# v12.net
KiCad netlist of a schematic drawn in EAGLE
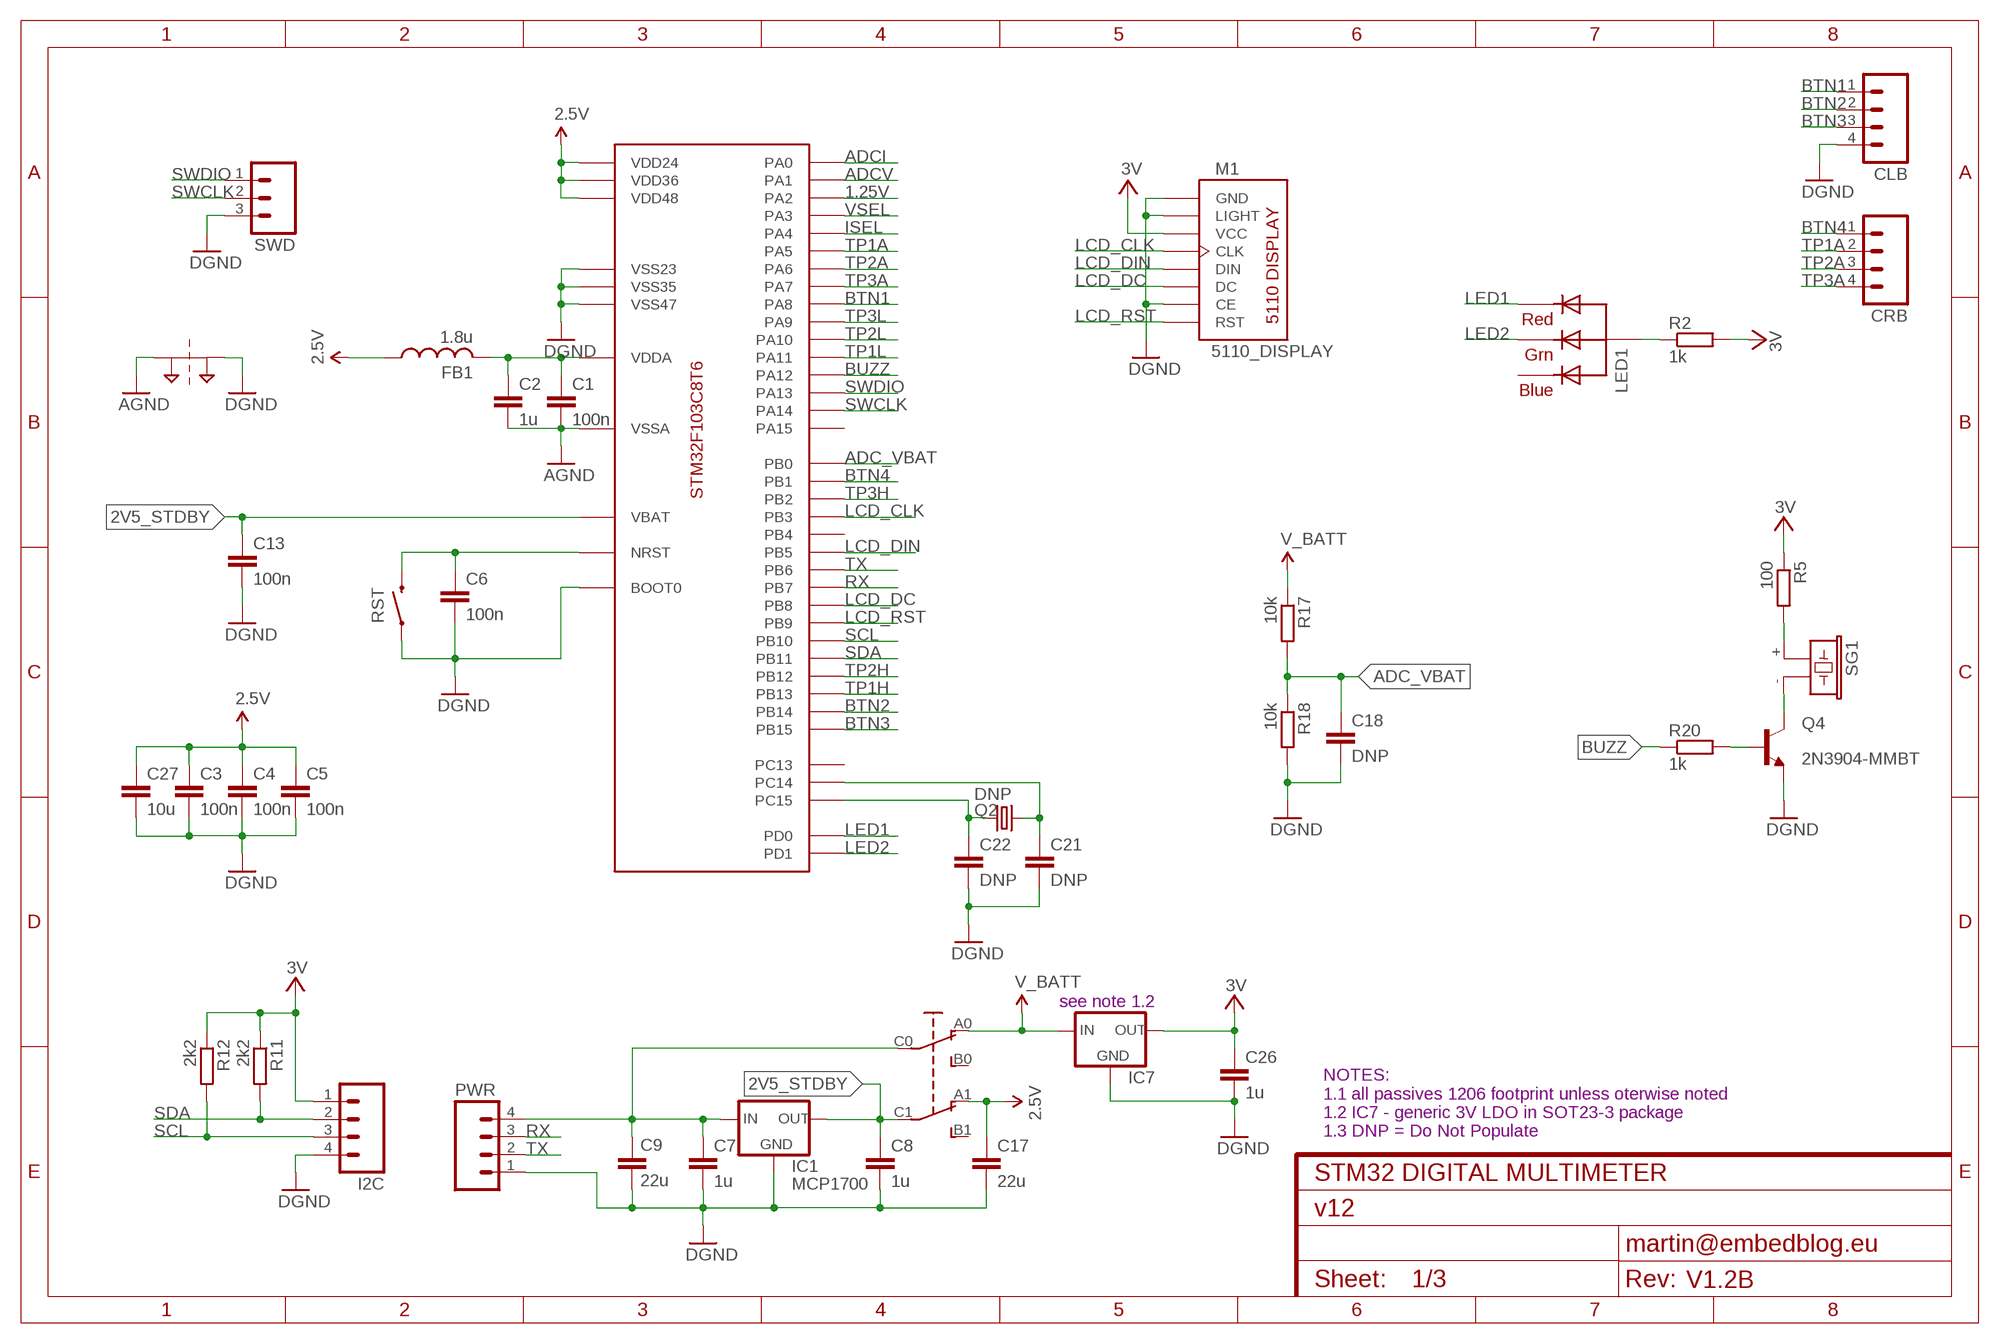
[diagram p0: schematic, sheet 1]
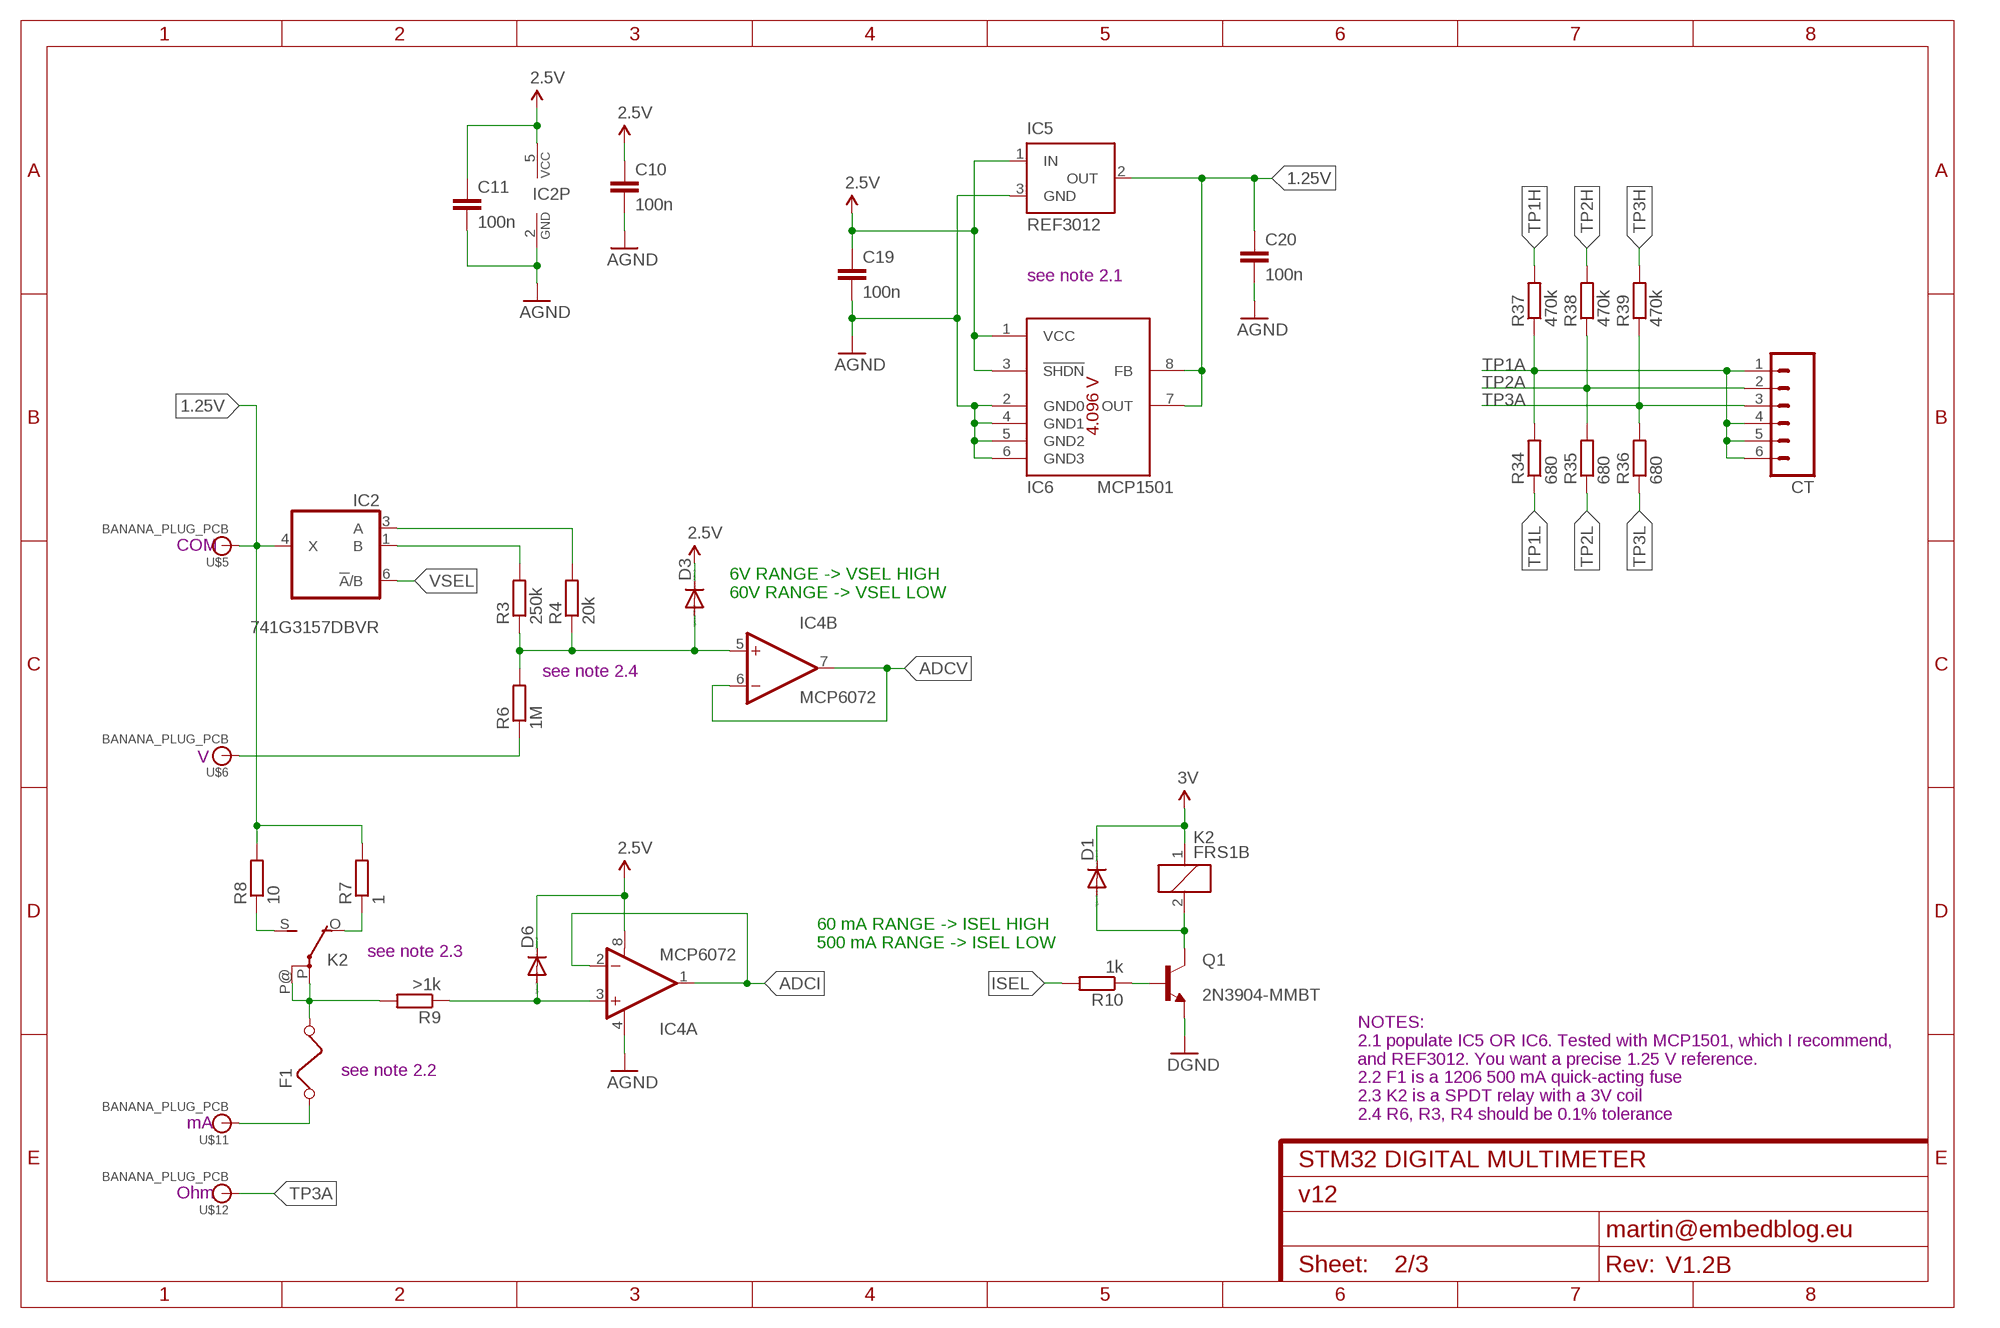
[diagram p1: schematic, sheet 2]
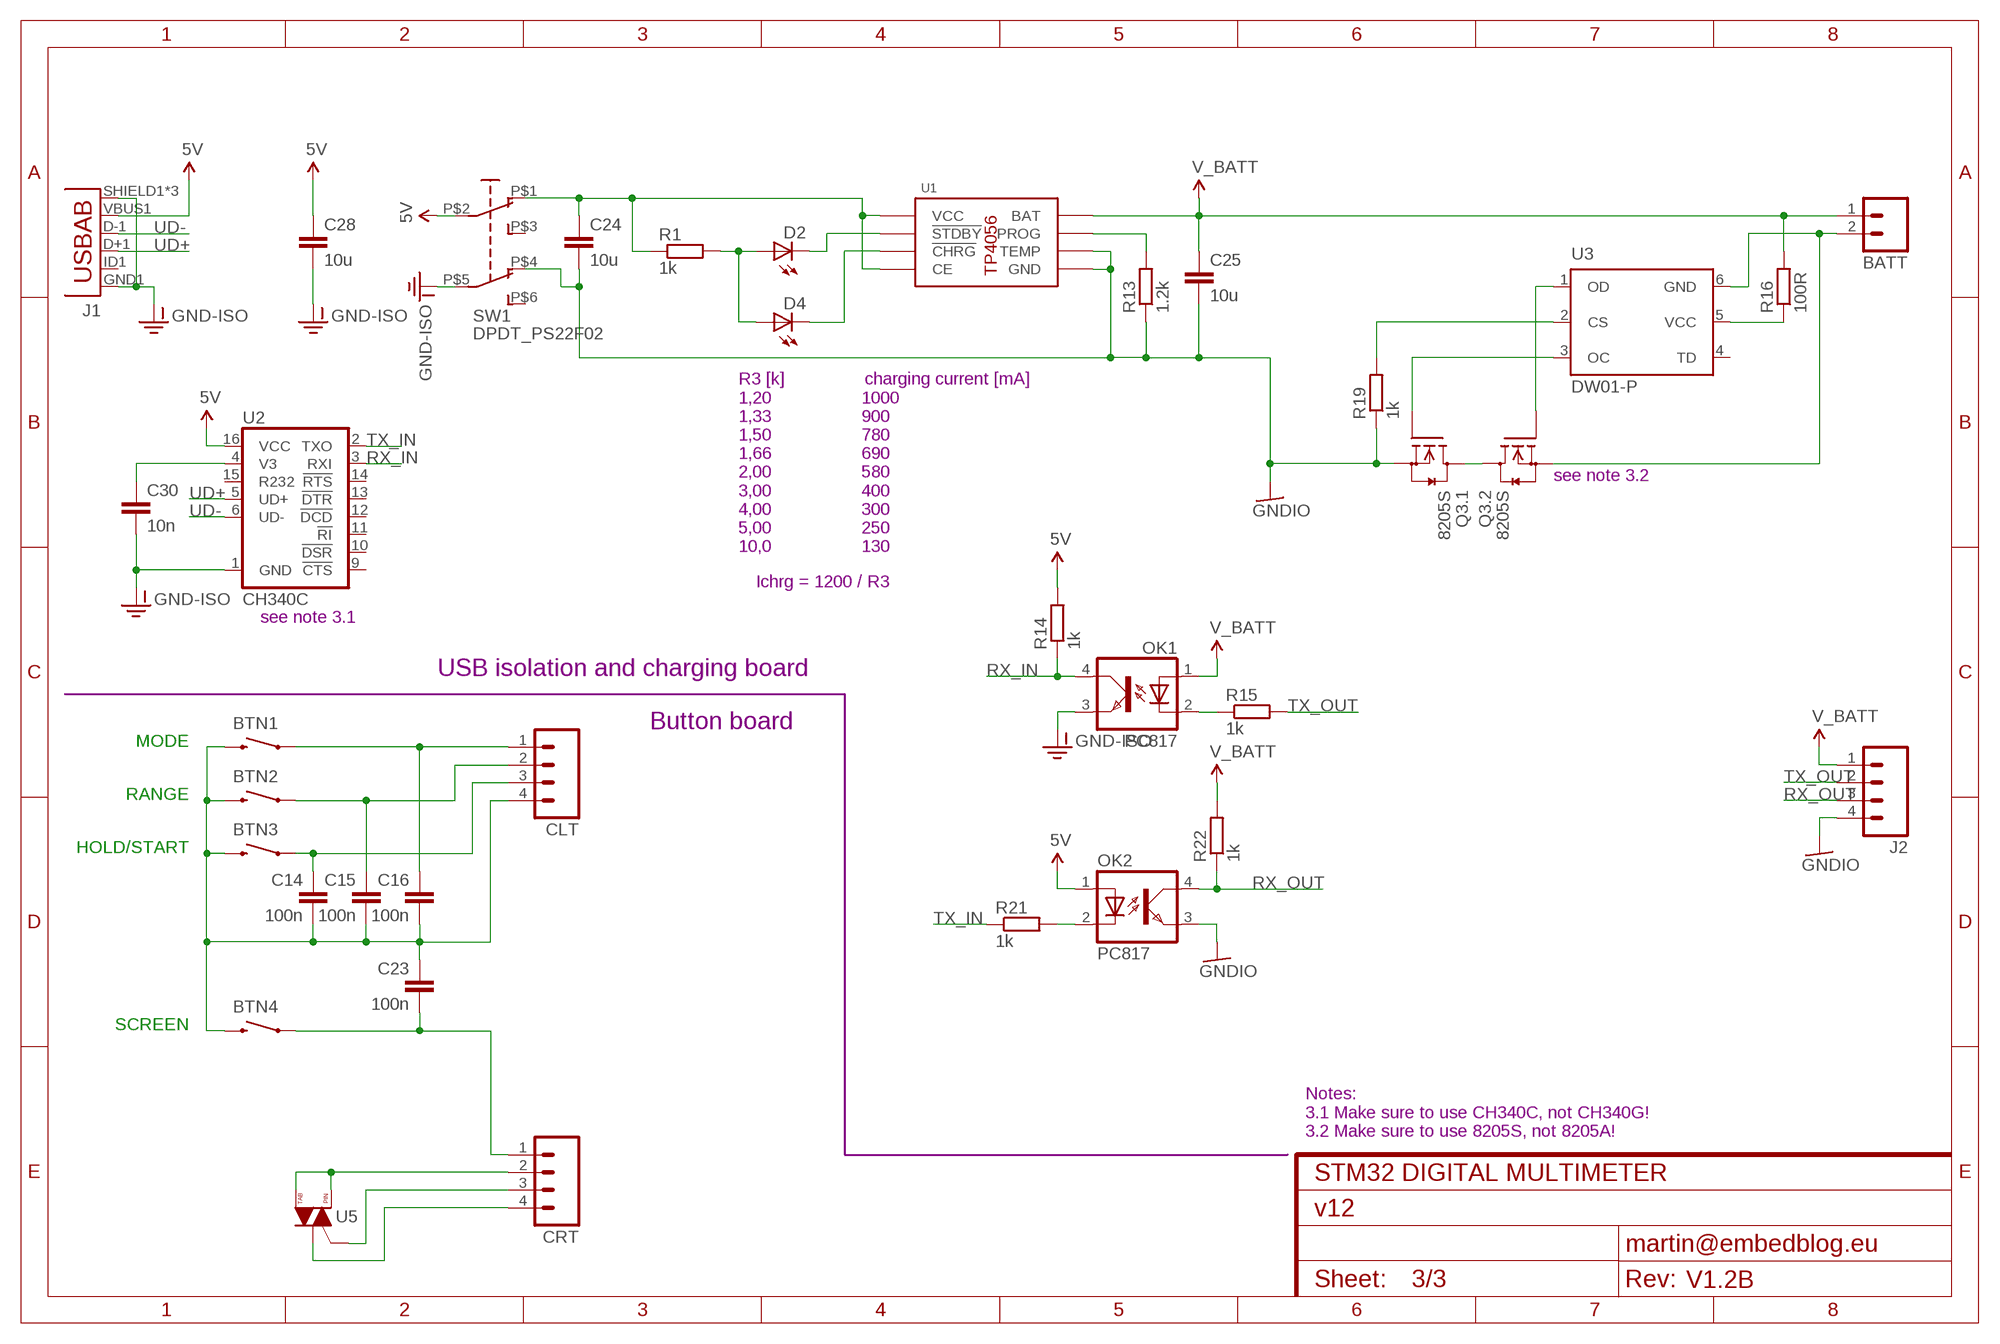
[diagram p2: schematic, sheet 3]

(export (version "E")
  (design (tool "Eeschema 10.0.6"))
  (components
    (comp (ref "C10")
      (value "100n")
      (footprint "eagle-import:1206")
      (libsource (lib "eagle-import") (part "CAP1206"))
    )
    (comp (ref "C11")
      (value "100n")
      (footprint "eagle-import:1206")
      (libsource (lib "eagle-import") (part "CAP1206"))
    )
    (comp (ref "C19")
      (value "100n")
      (footprint "eagle-import:C1206")
      (libsource (lib "eagle-import") (part "C-EUC1206"))
    )
    (comp (ref "C20")
      (value "100n")
      (footprint "eagle-import:C1206")
      (libsource (lib "eagle-import") (part "C-EUC1206"))
    )
    (comp (ref "CT")
      (value "M06SILK_FEMALE_PTH")
      (footprint "eagle-import:1X06")
      (libsource (lib "eagle-import") (part "M06SILK_FEMALE_PTH"))
    )
    (comp (ref "D1")
      (value "DIODE-MINIMELF")
      (footprint "eagle-import:MINIMELF")
      (libsource (lib "eagle-import") (part "DIODE-MINIMELF"))
    )
    (comp (ref "D3")
      (value "DIODE-MINIMELF")
      (footprint "eagle-import:MINIMELF")
      (libsource (lib "eagle-import") (part "DIODE-MINIMELF"))
    )
    (comp (ref "D6")
      (value "DIODE-MINIMELF")
      (footprint "eagle-import:MINIMELF")
      (libsource (lib "eagle-import") (part "DIODE-MINIMELF"))
    )
    (comp (ref "F1")
      (value "FUSEC")
      (footprint "eagle-import:1206")
      (libsource (lib "eagle-import") (part "FUSEC"))
    )
    (comp (ref "IC2")
      (value "741G3157DBVR")
      (footprint "eagle-import:DBV_R-PDSO-G6")
      (libsource (lib "eagle-import") (part "741G3157DBVR"))
    )
    (comp (ref "IC4")
      (value "MCP6072")
      (footprint "eagle-import:SO08")
      (libsource (lib "eagle-import") (part "OPAMP-DUALU"))
    )
    (comp (ref "IC5")
      (value "REF3012")
      (footprint "eagle-import:SOT23")
      (fields (field (name "MF") "MAXIM") (field (name "MPN") "MAX6520EUR-T"))
      (libsource (lib "eagle-import") (part "MAX6520"))
    )
    (comp (ref "IC6")
      (value "MCP1501")
      (footprint "eagle-import:SO08")
      (libsource (lib "eagle-import") (part "MCP1501"))
    )
    (comp (ref "K2")
      (value "FRS1B")
      (footprint "eagle-import:FRS1B")
      (libsource (lib "eagle-import") (part "FRS1B"))
    )
    (comp (ref "Q1")
      (value "2N3904-MMBT")
      (footprint "eagle-import:SOT23")
      (libsource (lib "eagle-import") (part "2N3904-MMBT"))
    )
    (comp (ref "R3")
      (value "250k")
      (footprint "eagle-import:R1206")
      (libsource (lib "eagle-import") (part "R-EU_R1206"))
    )
    (comp (ref "R4")
      (value "20k")
      (footprint "eagle-import:R1206")
      (libsource (lib "eagle-import") (part "R-EU_R1206"))
    )
    (comp (ref "R6")
      (value "1M")
      (footprint "eagle-import:R1206")
      (libsource (lib "eagle-import") (part "R-EU_R1206"))
    )
    (comp (ref "R7")
      (value "1")
      (footprint "eagle-import:R1206")
      (libsource (lib "eagle-import") (part "R-EU_R1206"))
    )
    (comp (ref "R8")
      (value "10")
      (footprint "eagle-import:R1206")
      (libsource (lib "eagle-import") (part "R-EU_R1206"))
    )
    (comp (ref "R9")
      (value ">1k")
      (footprint "eagle-import:R1206")
      (libsource (lib "eagle-import") (part "R-EU_R1206"))
    )
    (comp (ref "R10")
      (value "1k")
      (footprint "eagle-import:R1206")
      (libsource (lib "eagle-import") (part "R-EU_R1206"))
    )
    (comp (ref "R34")
      (value "680")
      (footprint "eagle-import:R1206")
      (libsource (lib "eagle-import") (part "R-EU_R1206"))
    )
    (comp (ref "R35")
      (value "680")
      (footprint "eagle-import:R1206")
      (libsource (lib "eagle-import") (part "R-EU_R1206"))
    )
    (comp (ref "R36")
      (value "680")
      (footprint "eagle-import:R1206")
      (libsource (lib "eagle-import") (part "R-EU_R1206"))
    )
    (comp (ref "R37")
      (value "470k")
      (footprint "eagle-import:R1206")
      (libsource (lib "eagle-import") (part "R-EU_R1206"))
    )
    (comp (ref "R38")
      (value "470k")
      (footprint "eagle-import:R1206")
      (libsource (lib "eagle-import") (part "R-EU_R1206"))
    )
    (comp (ref "R39")
      (value "470k")
      (footprint "eagle-import:R1206")
      (libsource (lib "eagle-import") (part "R-EU_R1206"))
    )
    (comp (ref "U$5")
      (value "BANANA_PLUG_PCB")
      (footprint "eagle-import:BANANA_6MMHOLE")
      (libsource (lib "eagle-import") (part "BANANA_PLUG_PCB"))
    )
    (comp (ref "U$6")
      (value "BANANA_PLUG_PCB")
      (footprint "eagle-import:BANANA_6MMHOLE")
      (libsource (lib "eagle-import") (part "BANANA_PLUG_PCB"))
    )
    (comp (ref "U$11")
      (value "BANANA_PLUG_PCB")
      (footprint "eagle-import:BANANA_6MMHOLE")
      (libsource (lib "eagle-import") (part "BANANA_PLUG_PCB"))
    )
    (comp (ref "U$12")
      (value "BANANA_PLUG_PCB")
      (footprint "eagle-import:BANANA_6MMHOLE")
      (libsource (lib "eagle-import") (part "BANANA_PLUG_PCB"))
    )
    (comp (ref "BATT")
      (value "M02PTH3")
      (footprint "eagle-import:1X02_LONGPADS")
      (libsource (lib "eagle-import") (part "M02PTH3"))
    )
    (comp (ref "BTN1")
      (value "SWITCH-MOMENTARY-2PTH")
      (footprint "eagle-import:TACTILE-PTH")
      (libsource (lib "eagle-import") (part "SWITCH-MOMENTARY-2PTH"))
    )
    (comp (ref "BTN2")
      (value "SWITCH-MOMENTARY-2PTH")
      (footprint "eagle-import:TACTILE-PTH")
      (libsource (lib "eagle-import") (part "SWITCH-MOMENTARY-2PTH"))
    )
    (comp (ref "BTN3")
      (value "SWITCH-MOMENTARY-2PTH")
      (footprint "eagle-import:TACTILE-PTH")
      (libsource (lib "eagle-import") (part "SWITCH-MOMENTARY-2PTH"))
    )
    (comp (ref "BTN4")
      (value "SWITCH-MOMENTARY-2PTH")
      (footprint "eagle-import:TACTILE-PTH")
      (libsource (lib "eagle-import") (part "SWITCH-MOMENTARY-2PTH"))
    )
    (comp (ref "C14")
      (value "100n")
      (footprint "eagle-import:C1206")
      (libsource (lib "eagle-import") (part "C-EUC1206"))
    )
    (comp (ref "C15")
      (value "100n")
      (footprint "eagle-import:C1206")
      (libsource (lib "eagle-import") (part "C-EUC1206"))
    )
    (comp (ref "C16")
      (value "100n")
      (footprint "eagle-import:C1206")
      (libsource (lib "eagle-import") (part "C-EUC1206"))
    )
    (comp (ref "C23")
      (value "100n")
      (footprint "eagle-import:C1206")
      (libsource (lib "eagle-import") (part "C-EUC1206"))
    )
    (comp (ref "C24")
      (value "10u")
      (footprint "eagle-import:C1206")
      (libsource (lib "eagle-import") (part "C-EUC1206"))
    )
    (comp (ref "C25")
      (value "10u")
      (footprint "eagle-import:C1206")
      (libsource (lib "eagle-import") (part "C-EUC1206"))
    )
    (comp (ref "C28")
      (value "10u")
      (footprint "eagle-import:C1206")
      (libsource (lib "eagle-import") (part "C-EUC1206"))
    )
    (comp (ref "C30")
      (value "10n")
      (footprint "eagle-import:C1206")
      (libsource (lib "eagle-import") (part "C-EUC1206"))
    )
    (comp (ref "CLT")
      (value "M04PTH")
      (footprint "eagle-import:1X04@1")
      (libsource (lib "eagle-import") (part "M04PTH"))
    )
    (comp (ref "CRT")
      (value "M04PTH")
      (footprint "eagle-import:1X04@1")
      (libsource (lib "eagle-import") (part "M04PTH"))
    )
    (comp (ref "D2")
      (value "LEDCHIPLED_1206")
      (footprint "eagle-import:CHIPLED_1206")
      (libsource (lib "eagle-import") (part "LEDCHIPLED_1206"))
    )
    (comp (ref "D4")
      (value "LEDCHIPLED_1206")
      (footprint "eagle-import:CHIPLED_1206")
      (libsource (lib "eagle-import") (part "LEDCHIPLED_1206"))
    )
    (comp (ref "J1")
      (value "USB-ABCONN-11794")
      (footprint "eagle-import:USB-AB-MICRO-SMD_V03")
      (libsource (lib "eagle-import") (part "USB-ABCONN-11794"))
    )
    (comp (ref "J2")
      (value "M04PTH")
      (footprint "eagle-import:1X04@1")
      (libsource (lib "eagle-import") (part "M04PTH"))
    )
    (comp (ref "OK1")
      (value "PC817")
      (footprint "eagle-import:DIL04")
      (fields (field (name "MPN") "PC817X4J000F"))
      (libsource (lib "eagle-import") (part "PC817"))
    )
    (comp (ref "OK2")
      (value "PC817")
      (footprint "eagle-import:DIL04")
      (fields (field (name "MPN") "PC817X4J000F"))
      (libsource (lib "eagle-import") (part "PC817"))
    )
    (comp (ref "Q3")
      (value "8205S")
      (footprint "eagle-import:SSOT-6")
      (libsource (lib "eagle-import") (part "FDC6305N"))
    )
    (comp (ref "R1")
      (value "1k")
      (footprint "eagle-import:R1206")
      (libsource (lib "eagle-import") (part "R-EU_R1206"))
    )
    (comp (ref "R13")
      (value "1.2k")
      (footprint "eagle-import:R1206")
      (libsource (lib "eagle-import") (part "R-EU_R1206"))
    )
    (comp (ref "R14")
      (value "1k")
      (footprint "eagle-import:R1206")
      (libsource (lib "eagle-import") (part "R-EU_R1206"))
    )
    (comp (ref "R15")
      (value "1k")
      (footprint "eagle-import:R1206")
      (libsource (lib "eagle-import") (part "R-EU_R1206"))
    )
    (comp (ref "R16")
      (value "100R")
      (footprint "eagle-import:R1206")
      (libsource (lib "eagle-import") (part "R-EU_R1206"))
    )
    (comp (ref "R19")
      (value "1k")
      (footprint "eagle-import:R1206")
      (libsource (lib "eagle-import") (part "R-EU_R1206"))
    )
    (comp (ref "R21")
      (value "1k")
      (footprint "eagle-import:R1206")
      (libsource (lib "eagle-import") (part "R-EU_R1206"))
    )
    (comp (ref "R22")
      (value "1k")
      (footprint "eagle-import:R1206")
      (libsource (lib "eagle-import") (part "R-EU_R1206"))
    )
    (comp (ref "SW1")
      (value "DPDT_PS22F02")
      (footprint "eagle-import:PS22_L02_DPDT_SW")
      (libsource (lib "eagle-import") (part "DPDT_PS22F02"))
    )
    (comp (ref "U1")
      (value "TP4056")
      (footprint "eagle-import:SOP8")
      (libsource (lib "eagle-import") (part "TP4056"))
    )
    (comp (ref "U2")
      (value "CH340C")
      (footprint "eagle-import:SO016")
      (libsource (lib "eagle-import") (part "CH340C"))
    )
    (comp (ref "U3")
      (value "DW01-P")
      (footprint "eagle-import:SOT23-6L")
      (libsource (lib "eagle-import") (part "DW01-P"))
    )
    (comp (ref "U5")
      (value "TRIAC-HPSMD")
      (footprint "eagle-import:SOT223")
      (libsource (lib "eagle-import") (part "TRIAC-HPSMD"))
    )
    (comp (ref "C1")
      (value "100n")
      (footprint "eagle-import:C1206")
      (libsource (lib "eagle-import") (part "C-EUC1206"))
    )
    (comp (ref "C2")
      (value "1u")
      (footprint "eagle-import:C1206")
      (libsource (lib "eagle-import") (part "C-EUC1206"))
    )
    (comp (ref "C3")
      (value "100n")
      (footprint "eagle-import:C1206")
      (libsource (lib "eagle-import") (part "C-EUC1206"))
    )
    (comp (ref "C4")
      (value "100n")
      (footprint "eagle-import:C1206")
      (libsource (lib "eagle-import") (part "C-EUC1206"))
    )
    (comp (ref "C5")
      (value "100n")
      (footprint "eagle-import:C1206")
      (libsource (lib "eagle-import") (part "C-EUC1206"))
    )
    (comp (ref "C6")
      (value "100n")
      (footprint "eagle-import:C1206")
      (libsource (lib "eagle-import") (part "C-EUC1206"))
    )
    (comp (ref "C7")
      (value "1u")
      (footprint "eagle-import:C1206")
      (libsource (lib "eagle-import") (part "C-EUC1206"))
    )
    (comp (ref "C8")
      (value "1u")
      (footprint "eagle-import:C1206")
      (libsource (lib "eagle-import") (part "C-EUC1206"))
    )
    (comp (ref "C9")
      (value "22u")
      (footprint "eagle-import:C1206")
      (libsource (lib "eagle-import") (part "C-EUC1206"))
    )
    (comp (ref "C13")
      (value "100n")
      (footprint "eagle-import:C1206")
      (libsource (lib "eagle-import") (part "C-EUC1206"))
    )
    (comp (ref "C17")
      (value "22u")
      (footprint "eagle-import:C1206")
      (libsource (lib "eagle-import") (part "C-EUC1206"))
    )
    (comp (ref "C18")
      (value "DNP")
      (footprint "eagle-import:C1206")
      (libsource (lib "eagle-import") (part "C-EUC1206"))
    )
    (comp (ref "C21")
      (value "DNP")
      (footprint "eagle-import:C1206")
      (libsource (lib "eagle-import") (part "C-EUC1206"))
    )
    (comp (ref "C22")
      (value "DNP")
      (footprint "eagle-import:C1206")
      (libsource (lib "eagle-import") (part "C-EUC1206"))
    )
    (comp (ref "C26")
      (value "1u")
      (footprint "eagle-import:C1206")
      (libsource (lib "eagle-import") (part "C-EUC1206"))
    )
    (comp (ref "C27")
      (value "10u")
      (footprint "eagle-import:C1206")
      (libsource (lib "eagle-import") (part "C-EUC1206"))
    )
    (comp (ref "CLB")
      (value "M04PTH")
      (footprint "eagle-import:1X04@1")
      (libsource (lib "eagle-import") (part "M04PTH"))
    )
    (comp (ref "CRB")
      (value "M04PTH")
      (footprint "eagle-import:1X04@1")
      (libsource (lib "eagle-import") (part "M04PTH"))
    )
    (comp (ref "FB1")
      (value "1.8u")
      (footprint "eagle-import:1206")
      (libsource (lib "eagle-import") (part "FERRITE-BEADC"))
    )
    (comp (ref "I2C")
      (value "M04PTH")
      (footprint "eagle-import:1X04@1")
      (libsource (lib "eagle-import") (part "M04PTH"))
    )
    (comp (ref "IC1")
      (value "MCP1700")
      (footprint "eagle-import:SOT23")
      (libsource (lib "eagle-import") (part "XC63FPM"))
    )
    (comp (ref "IC7")
      (value "XC63FPM")
      (footprint "eagle-import:SOT23")
      (libsource (lib "eagle-import") (part "XC63FPM"))
    )
    (comp (ref "LED1")
      (value "RGBLED_CA-5MM")
      (footprint "eagle-import:LED5MMRGB")
      (libsource (lib "eagle-import") (part "RGBLED_CA-5MM"))
    )
    (comp (ref "M1")
      (value "5110_DISPLAY")
      (footprint "eagle-import:5110_LAYOUT")
      (libsource (lib "eagle-import") (part "5110_DISPLAY"))
    )
    (comp (ref "PWR")
      (value "M04PTH")
      (footprint "eagle-import:1X04@1")
      (libsource (lib "eagle-import") (part "M04PTH"))
    )
    (comp (ref "Q2")
      (value "DNP")
      (footprint "eagle-import:TC26H")
      (libsource (lib "eagle-import") (part "CRYSTALTC26H"))
    )
    (comp (ref "Q4")
      (value "2N3904-MMBT")
      (footprint "eagle-import:SOT23")
      (libsource (lib "eagle-import") (part "2N3904-MMBT"))
    )
    (comp (ref "R2")
      (value "1k")
      (footprint "eagle-import:R1206")
      (libsource (lib "eagle-import") (part "R-EU_R1206"))
    )
    (comp (ref "R5")
      (value "100")
      (footprint "eagle-import:R1206")
      (libsource (lib "eagle-import") (part "R-EU_R1206"))
    )
    (comp (ref "R11")
      (value "2k2")
      (footprint "eagle-import:R1206")
      (libsource (lib "eagle-import") (part "R-EU_R1206"))
    )
    (comp (ref "R12")
      (value "2k2")
      (footprint "eagle-import:R1206")
      (libsource (lib "eagle-import") (part "R-EU_R1206"))
    )
    (comp (ref "R17")
      (value "10k")
      (footprint "eagle-import:R1206")
      (libsource (lib "eagle-import") (part "R-EU_R1206"))
    )
    (comp (ref "R18")
      (value "10k")
      (footprint "eagle-import:R1206")
      (libsource (lib "eagle-import") (part "R-EU_R1206"))
    )
    (comp (ref "R20")
      (value "1k")
      (footprint "eagle-import:R1206")
      (libsource (lib "eagle-import") (part "R-EU_R1206"))
    )
    (comp (ref "RST")
      (value "SWITCH-MOMENTARY-2SMD")
      (footprint "eagle-import:TACTILE-SWITCH-SMD")
      (libsource (lib "eagle-import") (part "SWITCH-MOMENTARY-2SMD"))
    )
    (comp (ref "SG1")
      (value "F/CM12P")
      (footprint "eagle-import:F_CM12P")
      (libsource (lib "eagle-import") (part "F/CM12P"))
    )
    (comp (ref "SJ1")
      (value "2PT_GND_TIE")
      (footprint "eagle-import:2PT_GND_TIE")
      (libsource (lib "eagle-import") (part "2PT_GND_TIE"))
    )
    (comp (ref "SWD")
      (value "M03PTH")
      (footprint "eagle-import:1X03")
      (libsource (lib "eagle-import") (part "M03PTH"))
    )
    (comp (ref "U$1")
      (value "STM32F103C8T6")
      (footprint "eagle-import:TQFP-48")
      (libsource (lib "eagle-import") (part "STM32F103C8T6"))
    )
    (comp (ref "U$16")
      (value "K3-2245_DPDT_SIDE_SWITCH")
      (footprint "eagle-import:K3-2245_DPDT_SWITCH")
      (libsource (lib "eagle-import") (part "K3-2245_DPDT_SIDE_SWITCH"))
    )
  )
  (nets
    (net (code "1") (name "1.25V") (class "Default")
      (node (ref "C20") (pin "1") (pinfunction "1_1") (pintype "passive"))
      (node (ref "IC2") (pin "4") (pinfunction "X_4") (pintype "bidirectional"))
      (node (ref "IC5") (pin "2") (pinfunction "OUT_2") (pintype "output"))
      (node (ref "IC6") (pin "7") (pinfunction "OUT_7") (pintype "bidirectional"))
      (node (ref "IC6") (pin "8") (pinfunction "FB_8") (pintype "bidirectional"))
      (node (ref "R7") (pin "2") (pinfunction "2_2") (pintype "passive"))
      (node (ref "R8") (pin "2") (pinfunction "2_2") (pintype "passive"))
      (node (ref "U$1") (pin "12") (pinfunction "PA2_12") (pintype "bidirectional"))
      (node (ref "U$5") (pin "P$1") (pinfunction "1_P$1") (pintype "passive"))
    )
    (net (code "2") (name "2.5V") (class "Default")
      (node (ref "C10") (pin "1") (pinfunction "1_1") (pintype "passive"))
      (node (ref "C11") (pin "1") (pinfunction "1_1") (pintype "passive"))
      (node (ref "C17") (pin "1") (pinfunction "1_1") (pintype "passive"))
      (node (ref "C19") (pin "1") (pinfunction "1_1") (pintype "passive"))
      (node (ref "C27") (pin "1") (pinfunction "1_1") (pintype "passive"))
      (node (ref "C3") (pin "1") (pinfunction "1_1") (pintype "passive"))
      (node (ref "C4") (pin "1") (pinfunction "1_1") (pintype "passive"))
      (node (ref "C5") (pin "1") (pinfunction "1_1") (pintype "passive"))
      (node (ref "D3") (pin "C") (pinfunction "C_C") (pintype "passive"))
      (node (ref "D6") (pin "C") (pinfunction "C_C") (pintype "passive"))
      (node (ref "FB1") (pin "1") (pinfunction "1_1") (pintype "passive"))
      (node (ref "IC2") (pin "5") (pinfunction "VCC_5") (pintype "power_in"))
      (node (ref "IC4") (pin "8") (pinfunction "V+_8") (pintype "power_in"))
      (node (ref "IC5") (pin "1") (pinfunction "IN_1") (pintype "input"))
      (node (ref "IC6") (pin "1") (pinfunction "VCC_1") (pintype "bidirectional"))
      (node (ref "IC6") (pin "3") (pinfunction "~{SHDN}_3") (pintype "bidirectional"))
      (node (ref "U$1") (pin "24") (pinfunction "VDD24_24") (pintype "input"))
      (node (ref "U$1") (pin "36") (pinfunction "VDD36_36") (pintype "input"))
      (node (ref "U$1") (pin "48") (pinfunction "VDD48_48") (pintype "input"))
      (node (ref "U$16") (pin "A1") (pinfunction "O1_A1") (pintype "passive"))
    )
    (net (code "3") (name "2V5_STDBY") (class "Default")
      (node (ref "C13") (pin "1") (pinfunction "1_1") (pintype "passive"))
      (node (ref "C8") (pin "1") (pinfunction "1_1") (pintype "passive"))
      (node (ref "IC1") (pin "2") (pinfunction "OUT_2") (pintype "passive"))
      (node (ref "U$1") (pin "1") (pinfunction "VBAT_1") (pintype "input"))
      (node (ref "U$16") (pin "C1") (pinfunction "P1_C1") (pintype "passive"))
    )
    (net (code "4") (name "3V") (class "Default")
      (node (ref "C26") (pin "1") (pinfunction "1_1") (pintype "passive"))
      (node (ref "D1") (pin "C") (pinfunction "C_C") (pintype "passive"))
      (node (ref "I2C") (pin "1") (pinfunction "1_1") (pintype "passive"))
      (node (ref "IC7") (pin "2") (pinfunction "OUT_2") (pintype "passive"))
      (node (ref "K2") (pin "1") (pinfunction "1_1") (pintype "passive"))
      (node (ref "M1") (pin "VCC") (pinfunction "VCC_VCC") (pintype "bidirectional"))
      (node (ref "R11") (pin "1") (pinfunction "1_1") (pintype "passive"))
      (node (ref "R12") (pin "1") (pinfunction "1_1") (pintype "passive"))
      (node (ref "R2") (pin "2") (pinfunction "2_2") (pintype "passive"))
      (node (ref "R5") (pin "1") (pinfunction "1_1") (pintype "passive"))
    )
    (net (code "5") (name "5V") (class "Default")
      (node (ref "C28") (pin "1") (pinfunction "1_1") (pintype "passive"))
      (node (ref "J1") (pin "VBUS1") (pinfunction "VBUS_VBUS1") (pintype "bidirectional"))
      (node (ref "OK2") (pin "1") (pinfunction "A_1") (pintype "passive"))
      (node (ref "R14") (pin "2") (pinfunction "2_2") (pintype "passive"))
      (node (ref "SW1") (pin "P$2") (pinfunction "P_P$2") (pintype "passive"))
      (node (ref "U2") (pin "16") (pinfunction "VCC_16") (pintype "bidirectional"))
    )
    (net (code "6") (name "ADCI") (class "Default")
      (node (ref "IC4") (pin "1") (pinfunction "OUT_1") (pintype "output"))
      (node (ref "IC4") (pin "2") (pinfunction "-IN_2") (pintype "input"))
      (node (ref "U$1") (pin "10") (pinfunction "PA0_10") (pintype "bidirectional"))
    )
    (net (code "7") (name "ADCV") (class "Default")
      (node (ref "IC4") (pin "6") (pinfunction "-IN_6") (pintype "input"))
      (node (ref "IC4") (pin "7") (pinfunction "OUT_7") (pintype "output"))
      (node (ref "U$1") (pin "11") (pinfunction "PA1_11") (pintype "bidirectional"))
    )
    (net (code "8") (name "ADC_VBAT") (class "Default")
      (node (ref "C18") (pin "1") (pinfunction "1_1") (pintype "passive"))
      (node (ref "R17") (pin "2") (pinfunction "2_2") (pintype "passive"))
      (node (ref "R18") (pin "1") (pinfunction "1_1") (pintype "passive"))
      (node (ref "U$1") (pin "18") (pinfunction "PB0_18") (pintype "bidirectional"))
    )
    (net (code "9") (name "AGND") (class "Default")
      (node (ref "C1") (pin "2") (pinfunction "2_2") (pintype "passive"))
      (node (ref "C10") (pin "2") (pinfunction "2_2") (pintype "passive"))
      (node (ref "C11") (pin "2") (pinfunction "2_2") (pintype "passive"))
      (node (ref "C19") (pin "2") (pinfunction "2_2") (pintype "passive"))
      (node (ref "C2") (pin "2") (pinfunction "2_2") (pintype "passive"))
      (node (ref "C20") (pin "2") (pinfunction "2_2") (pintype "passive"))
      (node (ref "IC2") (pin "2") (pinfunction "GND_2") (pintype "power_in"))
      (node (ref "IC4") (pin "4") (pinfunction "V-_4") (pintype "power_in"))
      (node (ref "IC5") (pin "3") (pinfunction "GND_3") (pintype "power_in"))
      (node (ref "IC6") (pin "2") (pinfunction "GND0_2") (pintype "bidirectional"))
      (node (ref "IC6") (pin "4") (pinfunction "GND1_4") (pintype "bidirectional"))
      (node (ref "IC6") (pin "5") (pinfunction "GND2_5") (pintype "bidirectional"))
      (node (ref "IC6") (pin "6") (pinfunction "GND3_6") (pintype "bidirectional"))
      (node (ref "SJ1") (pin "P$1") (pinfunction "P$1_P$1") (pintype "bidirectional"))
      (node (ref "U$1") (pin "8") (pinfunction "VSSA_8") (pintype "input"))
    )
    (net (code "10") (name "BTN1") (class "Default")
      (node (ref "CLB") (pin "1") (pinfunction "1_1") (pintype "passive"))
      (node (ref "U$1") (pin "29") (pinfunction "PA8_29") (pintype "bidirectional"))
    )
    (net (code "11") (name "BTN2") (class "Default")
      (node (ref "CLB") (pin "2") (pinfunction "2_2") (pintype "passive"))
      (node (ref "U$1") (pin "27") (pinfunction "PB14_27") (pintype "bidirectional"))
    )
    (net (code "12") (name "BTN3") (class "Default")
      (node (ref "CLB") (pin "3") (pinfunction "3_3") (pintype "passive"))
      (node (ref "U$1") (pin "28") (pinfunction "PB15_28") (pintype "bidirectional"))
    )
    (net (code "13") (name "BTN4") (class "Default")
      (node (ref "CRB") (pin "1") (pinfunction "1_1") (pintype "passive"))
      (node (ref "U$1") (pin "19") (pinfunction "PB1_19") (pintype "bidirectional"))
    )
    (net (code "14") (name "BUZZ") (class "Default")
      (node (ref "R20") (pin "1") (pinfunction "1_1") (pintype "passive"))
      (node (ref "U$1") (pin "33") (pinfunction "PA12_33") (pintype "bidirectional"))
    )
    (net (code "15") (name "GND") (class "Default")
      (node (ref "C13") (pin "2") (pinfunction "2_2") (pintype "passive"))
      (node (ref "C17") (pin "2") (pinfunction "2_2") (pintype "passive"))
      (node (ref "C18") (pin "2") (pinfunction "2_2") (pintype "passive"))
      (node (ref "C21") (pin "2") (pinfunction "2_2") (pintype "passive"))
      (node (ref "C22") (pin "2") (pinfunction "2_2") (pintype "passive"))
      (node (ref "C26") (pin "2") (pinfunction "2_2") (pintype "passive"))
      (node (ref "C27") (pin "2") (pinfunction "2_2") (pintype "passive"))
      (node (ref "C3") (pin "2") (pinfunction "2_2") (pintype "passive"))
      (node (ref "C4") (pin "2") (pinfunction "2_2") (pintype "passive"))
      (node (ref "C5") (pin "2") (pinfunction "2_2") (pintype "passive"))
      (node (ref "C6") (pin "2") (pinfunction "2_2") (pintype "passive"))
      (node (ref "C7") (pin "2") (pinfunction "2_2") (pintype "passive"))
      (node (ref "C8") (pin "2") (pinfunction "2_2") (pintype "passive"))
      (node (ref "C9") (pin "2") (pinfunction "2_2") (pintype "passive"))
      (node (ref "CLB") (pin "4") (pinfunction "4_4") (pintype "passive"))
      (node (ref "I2C") (pin "4") (pinfunction "4_4") (pintype "passive"))
      (node (ref "IC1") (pin "1") (pinfunction "GND_1") (pintype "input"))
      (node (ref "IC7") (pin "1") (pinfunction "GND_1") (pintype "input"))
      (node (ref "M1") (pin "CE") (pinfunction "CE_CE") (pintype "bidirectional"))
      (node (ref "M1") (pin "GND") (pinfunction "GND_GND") (pintype "bidirectional"))
      (node (ref "M1") (pin "LIGHT") (pinfunction "LIGHT_LIGHT") (pintype "bidirectional"))
      (node (ref "PWR") (pin "1") (pinfunction "1_1") (pintype "passive"))
      (node (ref "Q1") (pin "2") (pinfunction "E_2") (pintype "passive"))
      (node (ref "Q4") (pin "2") (pinfunction "E_2") (pintype "passive"))
      (node (ref "R18") (pin "2") (pinfunction "2_2") (pintype "passive"))
      (node (ref "RST") (pin "1") (pinfunction "1_1") (pintype "passive"))
      (node (ref "SJ1") (pin "P$2") (pinfunction "P$2_P$2") (pintype "bidirectional"))
      (node (ref "SWD") (pin "3") (pinfunction "3_3") (pintype "passive"))
      (node (ref "U$1") (pin "23") (pinfunction "VSS23_23") (pintype "input"))
      (node (ref "U$1") (pin "35") (pinfunction "VSS35_35") (pintype "input"))
      (node (ref "U$1") (pin "44") (pinfunction "BOOT0_44") (pintype "input"))
      (node (ref "U$1") (pin "47") (pinfunction "VSS47_47") (pintype "input"))
    )
    (net (code "16") (name "GND-ISO") (class "Default")
      (node (ref "C28") (pin "2") (pinfunction "2_2") (pintype "passive"))
      (node (ref "C30") (pin "2") (pinfunction "2_2") (pintype "passive"))
      (node (ref "J1") (pin "GND1") (pinfunction "GND_GND1") (pintype "bidirectional"))
      (node (ref "J1") (pin "SHIELD1") (pinfunction "SHIELD_SHIELD1") (pintype "bidirectional"))
      (node (ref "J1") (pin "SHIELD2") (pinfunction "SHIELD_SHIELD2") (pintype "bidirectional"))
      (node (ref "J1") (pin "SHIELD3") (pinfunction "SHIELD_SHIELD3") (pintype "bidirectional"))
      (node (ref "OK1") (pin "3") (pinfunction "EMIT_3") (pintype "passive"))
      (node (ref "SW1") (pin "P$5") (pinfunction "P1_P$5") (pintype "passive"))
      (node (ref "U2") (pin "1") (pinfunction "GND_1") (pintype "bidirectional"))
    )
    (net (code "17") (name "GNDIO") (class "Default")
      (node (ref "C24") (pin "2") (pinfunction "2_2") (pintype "passive"))
      (node (ref "C25") (pin "2") (pinfunction "2_2") (pintype "passive"))
      (node (ref "J2") (pin "4") (pinfunction "4_4") (pintype "passive"))
      (node (ref "OK2") (pin "3") (pinfunction "EMIT_3") (pintype "passive"))
      (node (ref "Q3") (pin "5") (pinfunction "S_5") (pintype "passive"))
      (node (ref "R13") (pin "1") (pinfunction "1_1") (pintype "passive"))
      (node (ref "R19") (pin "1") (pinfunction "1_1") (pintype "passive"))
      (node (ref "SW1") (pin "P$4") (pinfunction "O1_P$4") (pintype "passive"))
      (node (ref "U1") (pin "1") (pinfunction "TEMP_1") (pintype "bidirectional"))
      (node (ref "U1") (pin "3") (pinfunction "GND_3") (pintype "bidirectional"))
    )
    (net (code "18") (name "ISEL") (class "Default")
      (node (ref "R10") (pin "2") (pinfunction "2_2") (pintype "passive"))
      (node (ref "U$1") (pin "14") (pinfunction "PA4_14") (pintype "bidirectional"))
    )
    (net (code "19") (name "LCD_CLK") (class "Default")
      (node (ref "M1") (pin "CLK") (pinfunction "CLK_CLK") (pintype "bidirectional"))
      (node (ref "U$1") (pin "39") (pinfunction "PB3_39") (pintype "bidirectional"))
    )
    (net (code "20") (name "LCD_DC") (class "Default")
      (node (ref "M1") (pin "DC") (pinfunction "DC_DC") (pintype "bidirectional"))
      (node (ref "U$1") (pin "45") (pinfunction "PB8_45") (pintype "bidirectional"))
    )
    (net (code "21") (name "LCD_DIN") (class "Default")
      (node (ref "M1") (pin "DIN") (pinfunction "DIN_DIN") (pintype "bidirectional"))
      (node (ref "U$1") (pin "41") (pinfunction "PB5_41") (pintype "bidirectional"))
    )
    (net (code "22") (name "LCD_RST") (class "Default")
      (node (ref "M1") (pin "RST") (pinfunction "RST_RST") (pintype "bidirectional"))
      (node (ref "U$1") (pin "46") (pinfunction "PB9_46") (pintype "bidirectional"))
    )
    (net (code "23") (name "LED1") (class "Default")
      (node (ref "LED1") (pin "1") (pinfunction "RED_1") (pintype "bidirectional"))
      (node (ref "U$1") (pin "5") (pinfunction "PD0_5") (pintype "bidirectional"))
    )
    (net (code "24") (name "LED2") (class "Default")
      (node (ref "LED1") (pin "3") (pinfunction "GREEN_3") (pintype "bidirectional"))
      (node (ref "U$1") (pin "6") (pinfunction "PD1_6") (pintype "bidirectional"))
    )
    (net (code "25") (name "Net-(BTN1-2)") (class "Default")
      (node (ref "BTN1") (pin "3") (pinfunction "2_3") (pintype "passive"))
      (node (ref "BTN2") (pin "3") (pinfunction "2_3") (pintype "passive"))
      (node (ref "BTN3") (pin "3") (pinfunction "2_3") (pintype "passive"))
      (node (ref "BTN4") (pin "3") (pinfunction "2_3") (pintype "passive"))
      (node (ref "C14") (pin "2") (pinfunction "2_2") (pintype "passive"))
      (node (ref "C15") (pin "2") (pinfunction "2_2") (pintype "passive"))
      (node (ref "C16") (pin "2") (pinfunction "2_2") (pintype "passive"))
      (node (ref "C23") (pin "1") (pinfunction "1_1") (pintype "passive"))
      (node (ref "CLT") (pin "4") (pinfunction "4_4") (pintype "passive"))
    )
    (net (code "26") (name "Net-(BTN1-Pad1)") (class "Default")
      (node (ref "BTN1") (pin "1") (pinfunction "1_1") (pintype "passive"))
      (node (ref "C16") (pin "1") (pinfunction "1_1") (pintype "passive"))
      (node (ref "CLT") (pin "1") (pinfunction "1_1") (pintype "passive"))
    )
    (net (code "27") (name "Net-(BTN2-Pad1)") (class "Default")
      (node (ref "BTN2") (pin "1") (pinfunction "1_1") (pintype "passive"))
      (node (ref "C15") (pin "1") (pinfunction "1_1") (pintype "passive"))
      (node (ref "CLT") (pin "2") (pinfunction "2_2") (pintype "passive"))
    )
    (net (code "28") (name "Net-(BTN3-Pad1)") (class "Default")
      (node (ref "BTN3") (pin "1") (pinfunction "1_1") (pintype "passive"))
      (node (ref "C14") (pin "1") (pinfunction "1_1") (pintype "passive"))
      (node (ref "CLT") (pin "3") (pinfunction "3_3") (pintype "passive"))
    )
    (net (code "29") (name "Net-(BTN4-Pad1)") (class "Default")
      (node (ref "BTN4") (pin "1") (pinfunction "1_1") (pintype "passive"))
      (node (ref "C23") (pin "2") (pinfunction "2_2") (pintype "passive"))
      (node (ref "CRT") (pin "1") (pinfunction "1_1") (pintype "passive"))
    )
    (net (code "30") (name "Net-(CRT-Pad2)") (class "Default")
      (node (ref "CRT") (pin "2") (pinfunction "2_2") (pintype "passive"))
      (node (ref "U5") (pin "2") (pinfunction "T2_2") (pintype "passive"))
      (node (ref "U5") (pin "4") (pinfunction "T2_4") (pintype "passive"))
    )
    (net (code "31") (name "Net-(D2-PadA)") (class "Default")
      (node (ref "D2") (pin "A") (pinfunction "A_A") (pintype "passive"))
      (node (ref "D4") (pin "A") (pinfunction "A_A") (pintype "passive"))
      (node (ref "R1") (pin "2") (pinfunction "2_2") (pintype "passive"))
    )
    (net (code "32") (name "Net-(F1-Pad2)") (class "Default")
      (node (ref "F1") (pin "2") (pinfunction "2_2") (pintype "passive"))
      (node (ref "K2") (pin "P") (pinfunction "P_P") (pintype "passive"))
      (node (ref "K2") (pin "P@") (pinfunction "P_P@") (pintype "passive"))
      (node (ref "R9") (pin "2") (pinfunction "2_2") (pintype "passive"))
    )
    (net (code "33") (name "Net-(IC1-IN)") (class "Default")
      (node (ref "C7") (pin "1") (pinfunction "1_1") (pintype "passive"))
      (node (ref "C9") (pin "1") (pinfunction "1_1") (pintype "passive"))
      (node (ref "IC1") (pin "3") (pinfunction "IN_3") (pintype "input"))
      (node (ref "PWR") (pin "4") (pinfunction "4_4") (pintype "passive"))
      (node (ref "U$16") (pin "C0") (pinfunction "P_C0") (pintype "passive"))
    )
    (net (code "34") (name "Net-(IC2A-A)") (class "Default")
      (node (ref "IC2") (pin "3") (pinfunction "A_3") (pintype "bidirectional"))
      (node (ref "R4") (pin "2") (pinfunction "2_2") (pintype "passive"))
    )
    (net (code "35") (name "Net-(IC2A-B)") (class "Default")
      (node (ref "IC2") (pin "1") (pinfunction "B_1") (pintype "bidirectional"))
      (node (ref "R3") (pin "2") (pinfunction "2_2") (pintype "passive"))
    )
    (net (code "36") (name "Net-(IC4A-+IN)") (class "Default")
      (node (ref "D6") (pin "A") (pinfunction "A_A") (pintype "passive"))
      (node (ref "IC4") (pin "3") (pinfunction "+IN_3") (pintype "input"))
      (node (ref "R9") (pin "1") (pinfunction "1_1") (pintype "passive"))
    )
    (net (code "37") (name "Net-(IC4B-+IN)") (class "Default")
      (node (ref "D3") (pin "A") (pinfunction "A_A") (pintype "passive"))
      (node (ref "IC4") (pin "5") (pinfunction "+IN_5") (pintype "input"))
      (node (ref "R3") (pin "1") (pinfunction "1_1") (pintype "passive"))
      (node (ref "R4") (pin "1") (pinfunction "1_1") (pintype "passive"))
      (node (ref "R6") (pin "2") (pinfunction "2_2") (pintype "passive"))
    )
    (net (code "38") (name "Net-(K2-PadO)") (class "Default")
      (node (ref "K2") (pin "O") (pinfunction "O_O") (pintype "passive"))
      (node (ref "R7") (pin "1") (pinfunction "1_1") (pintype "passive"))
    )
    (net (code "39") (name "Net-(K2-PadS)") (class "Default")
      (node (ref "K2") (pin "S") (pinfunction "S_S") (pintype "passive"))
      (node (ref "R8") (pin "1") (pinfunction "1_1") (pintype "passive"))
    )
    (net (code "40") (name "Net-(LED1-VCC)") (class "Default")
      (node (ref "LED1") (pin "2") (pinfunction "VCC_2") (pintype "bidirectional"))
      (node (ref "R2") (pin "1") (pinfunction "1_1") (pintype "passive"))
    )
    (net (code "41") (name "Net-(OK1-C)") (class "Default")
      (node (ref "OK1") (pin "2") (pinfunction "C_2") (pintype "passive"))
      (node (ref "R15") (pin "1") (pinfunction "1_1") (pintype "passive"))
    )
    (net (code "42") (name "Net-(OK2-C)") (class "Default")
      (node (ref "OK2") (pin "2") (pinfunction "C_2") (pintype "passive"))
      (node (ref "R21") (pin "2") (pinfunction "2_2") (pintype "passive"))
    )
    (net (code "43") (name "Net-(Q1-B)") (class "Default")
      (node (ref "Q1") (pin "1") (pinfunction "B_1") (pintype "passive"))
      (node (ref "R10") (pin "1") (pinfunction "1_1") (pintype "passive"))
    )
    (net (code "44") (name "Net-(Q1-C)") (class "Default")
      (node (ref "D1") (pin "A") (pinfunction "A_A") (pintype "passive"))
      (node (ref "K2") (pin "2") (pinfunction "2_2") (pintype "passive"))
      (node (ref "Q1") (pin "3") (pinfunction "C_3") (pintype "passive"))
    )
    (net (code "45") (name "Net-(Q3A-D)") (class "Default")
      (node (ref "Q3") (pin "4") (pinfunction "D_4") (pintype "passive"))
      (node (ref "Q3") (pin "6") (pinfunction "D_6") (pintype "passive"))
    )
    (net (code "46") (name "Net-(Q3A-G)") (class "Default")
      (node (ref "Q3") (pin "1") (pinfunction "G_1") (pintype "passive"))
      (node (ref "U3") (pin "3") (pinfunction "OC_3") (pintype "power_in"))
    )
    (net (code "47") (name "Net-(Q3B-G)") (class "Default")
      (node (ref "Q3") (pin "3") (pinfunction "G_3") (pintype "passive"))
      (node (ref "U3") (pin "1") (pinfunction "OD_1") (pintype "power_in"))
    )
    (net (code "48") (name "Net-(Q3B-S)") (class "Default")
      (node (ref "BATT") (pin "2") (pinfunction "2_2") (pintype "passive"))
      (node (ref "Q3") (pin "2") (pinfunction "S_2") (pintype "passive"))
      (node (ref "U3") (pin "6") (pinfunction "GND_6") (pintype "output"))
    )
    (net (code "49") (name "Net-(Q4-B)") (class "Default")
      (node (ref "Q4") (pin "1") (pinfunction "B_1") (pintype "passive"))
      (node (ref "R20") (pin "2") (pinfunction "2_2") (pintype "passive"))
    )
    (net (code "50") (name "Net-(Q4-C)") (class "Default")
      (node (ref "Q4") (pin "3") (pinfunction "C_3") (pintype "passive"))
      (node (ref "SG1") (pin "-") (pinfunction "2_-") (pintype "passive"))
    )
    (net (code "51") (name "Net-(RST-2)") (class "Default")
      (node (ref "C6") (pin "1") (pinfunction "1_1") (pintype "passive"))
      (node (ref "RST") (pin "3") (pinfunction "2_3") (pintype "passive"))
      (node (ref "U$1") (pin "7") (pinfunction "NRST_7") (pintype "input"))
    )
    (net (code "52") (name "Net-(SG1-1)") (class "Default")
      (node (ref "R5") (pin "2") (pinfunction "2_2") (pintype "passive"))
      (node (ref "SG1") (pin "+") (pinfunction "1_+") (pintype "passive"))
    )
    (net (code "53") (name "Net-(SW1-O)") (class "Default")
      (node (ref "C24") (pin "1") (pinfunction "1_1") (pintype "passive"))
      (node (ref "R1") (pin "1") (pinfunction "1_1") (pintype "passive"))
      (node (ref "SW1") (pin "P$1") (pinfunction "O_P$1") (pintype "passive"))
      (node (ref "U1") (pin "4") (pinfunction "VCC_4") (pintype "bidirectional"))
      (node (ref "U1") (pin "8") (pinfunction "CE_8") (pintype "bidirectional"))
    )
    (net (code "54") (name "Net-(U$1-PC14)") (class "Default")
      (node (ref "C21") (pin "1") (pinfunction "1_1") (pintype "passive"))
      (node (ref "Q2") (pin "2") (pinfunction "2_2") (pintype "passive"))
      (node (ref "U$1") (pin "3") (pinfunction "PC14_3") (pintype "bidirectional"))
    )
    (net (code "55") (name "Net-(U$1-PC15)") (class "Default")
      (node (ref "C22") (pin "1") (pinfunction "1_1") (pintype "passive"))
      (node (ref "Q2") (pin "1") (pinfunction "1_1") (pintype "passive"))
      (node (ref "U$1") (pin "4") (pinfunction "PC15_4") (pintype "bidirectional"))
    )
    (net (code "56") (name "Net-(U$1-VDDA)") (class "Default")
      (node (ref "C1") (pin "1") (pinfunction "1_1") (pintype "passive"))
      (node (ref "C2") (pin "1") (pinfunction "1_1") (pintype "passive"))
      (node (ref "FB1") (pin "2") (pinfunction "2_2") (pintype "passive"))
      (node (ref "U$1") (pin "9") (pinfunction "VDDA_9") (pintype "input"))
    )
    (net (code "57") (name "Net-(U$6-1)") (class "Default")
      (node (ref "R6") (pin "1") (pinfunction "1_1") (pintype "passive"))
      (node (ref "U$6") (pin "P$1") (pinfunction "1_P$1") (pintype "passive"))
    )
    (net (code "58") (name "Net-(U$11-1)") (class "Default")
      (node (ref "F1") (pin "1") (pinfunction "1_1") (pintype "passive"))
      (node (ref "U$11") (pin "P$1") (pinfunction "1_P$1") (pintype "passive"))
    )
    (net (code "59") (name "Net-(U1-PROG)") (class "Default")
      (node (ref "R13") (pin "2") (pinfunction "2_2") (pintype "passive"))
      (node (ref "U1") (pin "2") (pinfunction "PROG_2") (pintype "bidirectional"))
    )
    (net (code "60") (name "Net-(U1-~{CHRG})") (class "Default")
      (node (ref "D4") (pin "C") (pinfunction "C_C") (pintype "passive"))
      (node (ref "U1") (pin "7") (pinfunction "~{CHRG}_7") (pintype "bidirectional"))
    )
    (net (code "61") (name "Net-(U1-~{STDBY})") (class "Default")
      (node (ref "D2") (pin "C") (pinfunction "C_C") (pintype "passive"))
      (node (ref "U1") (pin "6") (pinfunction "~{STDBY}_6") (pintype "bidirectional"))
    )
    (net (code "62") (name "Net-(U2-V3)") (class "Default")
      (node (ref "C30") (pin "1") (pinfunction "1_1") (pintype "passive"))
      (node (ref "U2") (pin "4") (pinfunction "V3_4") (pintype "bidirectional"))
    )
    (net (code "63") (name "Net-(U3-CS)") (class "Default")
      (node (ref "R19") (pin "2") (pinfunction "2_2") (pintype "passive"))
      (node (ref "U3") (pin "2") (pinfunction "CS_2") (pintype "input"))
    )
    (net (code "64") (name "Net-(U3-VCC)") (class "Default")
      (node (ref "R16") (pin "1") (pinfunction "1_1") (pintype "passive"))
      (node (ref "U3") (pin "5") (pinfunction "VCC_5") (pintype "input"))
    )
    (net (code "65") (name "Net-(U5-G)") (class "Default")
      (node (ref "CRT") (pin "3") (pinfunction "3_3") (pintype "passive"))
      (node (ref "U5") (pin "3") (pinfunction "G_3") (pintype "bidirectional"))
    )
    (net (code "66") (name "Net-(U5-T1)") (class "Default")
      (node (ref "CRT") (pin "4") (pinfunction "4_4") (pintype "passive"))
      (node (ref "U5") (pin "1") (pinfunction "T1_1") (pintype "bidirectional"))
    )
    (net (code "67") (name "RX") (class "Default")
      (node (ref "PWR") (pin "3") (pinfunction "3_3") (pintype "passive"))
      (node (ref "U$1") (pin "43") (pinfunction "PB7_43") (pintype "bidirectional"))
    )
    (net (code "68") (name "RX_IN") (class "Default")
      (node (ref "OK1") (pin "4") (pinfunction "COL_4") (pintype "passive"))
      (node (ref "R14") (pin "1") (pinfunction "1_1") (pintype "passive"))
      (node (ref "U2") (pin "3") (pinfunction "RXI_3") (pintype "bidirectional"))
    )
    (net (code "69") (name "RX_OUT") (class "Default")
      (node (ref "J2") (pin "3") (pinfunction "3_3") (pintype "passive"))
      (node (ref "OK2") (pin "4") (pinfunction "COL_4") (pintype "passive"))
      (node (ref "R22") (pin "1") (pinfunction "1_1") (pintype "passive"))
    )
    (net (code "70") (name "SCL") (class "Default")
      (node (ref "I2C") (pin "3") (pinfunction "3_3") (pintype "passive"))
      (node (ref "R12") (pin "2") (pinfunction "2_2") (pintype "passive"))
      (node (ref "U$1") (pin "21") (pinfunction "PB10_21") (pintype "bidirectional"))
    )
    (net (code "71") (name "SDA") (class "Default")
      (node (ref "I2C") (pin "2") (pinfunction "2_2") (pintype "passive"))
      (node (ref "R11") (pin "2") (pinfunction "2_2") (pintype "passive"))
      (node (ref "U$1") (pin "22") (pinfunction "PB11_22") (pintype "bidirectional"))
    )
    (net (code "72") (name "SWCLK") (class "Default")
      (node (ref "SWD") (pin "2") (pinfunction "2_2") (pintype "passive"))
      (node (ref "U$1") (pin "37") (pinfunction "PA14_37") (pintype "bidirectional"))
    )
    (net (code "73") (name "SWDIO") (class "Default")
      (node (ref "SWD") (pin "1") (pinfunction "1_1") (pintype "passive"))
      (node (ref "U$1") (pin "34") (pinfunction "PA13_34") (pintype "bidirectional"))
    )
    (net (code "74") (name "TP1A") (class "Default")
      (node (ref "CRB") (pin "2") (pinfunction "2_2") (pintype "passive"))
      (node (ref "CT") (pin "1") (pinfunction "1_1") (pintype "passive"))
      (node (ref "CT") (pin "4") (pinfunction "4_4") (pintype "passive"))
      (node (ref "CT") (pin "5") (pinfunction "5_5") (pintype "passive"))
      (node (ref "CT") (pin "6") (pinfunction "6_6") (pintype "passive"))
      (node (ref "R34") (pin "2") (pinfunction "2_2") (pintype "passive"))
      (node (ref "R37") (pin "1") (pinfunction "1_1") (pintype "passive"))
      (node (ref "U$1") (pin "15") (pinfunction "PA5_15") (pintype "bidirectional"))
    )
    (net (code "75") (name "TP1H") (class "Default")
      (node (ref "R37") (pin "2") (pinfunction "2_2") (pintype "passive"))
      (node (ref "U$1") (pin "26") (pinfunction "PB13_26") (pintype "bidirectional"))
    )
    (net (code "76") (name "TP1L") (class "Default")
      (node (ref "R34") (pin "1") (pinfunction "1_1") (pintype "passive"))
      (node (ref "U$1") (pin "32") (pinfunction "PA11_32") (pintype "bidirectional"))
    )
    (net (code "77") (name "TP2A") (class "Default")
      (node (ref "CRB") (pin "3") (pinfunction "3_3") (pintype "passive"))
      (node (ref "CT") (pin "2") (pinfunction "2_2") (pintype "passive"))
      (node (ref "R35") (pin "2") (pinfunction "2_2") (pintype "passive"))
      (node (ref "R38") (pin "1") (pinfunction "1_1") (pintype "passive"))
      (node (ref "U$1") (pin "16") (pinfunction "PA6_16") (pintype "bidirectional"))
    )
    (net (code "78") (name "TP2H") (class "Default")
      (node (ref "R38") (pin "2") (pinfunction "2_2") (pintype "passive"))
      (node (ref "U$1") (pin "25") (pinfunction "PB12_25") (pintype "bidirectional"))
    )
    (net (code "79") (name "TP2L") (class "Default")
      (node (ref "R35") (pin "1") (pinfunction "1_1") (pintype "passive"))
      (node (ref "U$1") (pin "31") (pinfunction "PA10_31") (pintype "bidirectional"))
    )
    (net (code "80") (name "TP3A") (class "Default")
      (node (ref "CRB") (pin "4") (pinfunction "4_4") (pintype "passive"))
      (node (ref "CT") (pin "3") (pinfunction "3_3") (pintype "passive"))
      (node (ref "R36") (pin "2") (pinfunction "2_2") (pintype "passive"))
      (node (ref "R39") (pin "1") (pinfunction "1_1") (pintype "passive"))
      (node (ref "U$1") (pin "17") (pinfunction "PA7_17") (pintype "bidirectional"))
      (node (ref "U$12") (pin "P$1") (pinfunction "1_P$1") (pintype "passive"))
    )
    (net (code "81") (name "TP3H") (class "Default")
      (node (ref "R39") (pin "2") (pinfunction "2_2") (pintype "passive"))
      (node (ref "U$1") (pin "20") (pinfunction "PB2_20") (pintype "bidirectional"))
    )
    (net (code "82") (name "TP3L") (class "Default")
      (node (ref "R36") (pin "1") (pinfunction "1_1") (pintype "passive"))
      (node (ref "U$1") (pin "30") (pinfunction "PA9_30") (pintype "bidirectional"))
    )
    (net (code "83") (name "TX") (class "Default")
      (node (ref "PWR") (pin "2") (pinfunction "2_2") (pintype "passive"))
      (node (ref "U$1") (pin "42") (pinfunction "PB6_42") (pintype "bidirectional"))
    )
    (net (code "84") (name "TX_IN") (class "Default")
      (node (ref "R21") (pin "1") (pinfunction "1_1") (pintype "passive"))
      (node (ref "U2") (pin "2") (pinfunction "TXO_2") (pintype "bidirectional"))
    )
    (net (code "85") (name "TX_OUT") (class "Default")
      (node (ref "J2") (pin "2") (pinfunction "2_2") (pintype "passive"))
      (node (ref "R15") (pin "2") (pinfunction "2_2") (pintype "passive"))
    )
    (net (code "86") (name "UD+") (class "Default")
      (node (ref "J1") (pin "D+1") (pinfunction "D+_D+1") (pintype "bidirectional"))
      (node (ref "U2") (pin "5") (pinfunction "UD+_5") (pintype "bidirectional"))
    )
    (net (code "87") (name "UD-") (class "Default")
      (node (ref "J1") (pin "D-1") (pinfunction "D-_D-1") (pintype "bidirectional"))
      (node (ref "U2") (pin "6") (pinfunction "UD-_6") (pintype "bidirectional"))
    )
    (net (code "88") (name "VSEL") (class "Default")
      (node (ref "IC2") (pin "6") (pinfunction "~{A}/B_6") (pintype "input"))
      (node (ref "U$1") (pin "13") (pinfunction "PA3_13") (pintype "bidirectional"))
    )
    (net (code "89") (name "V_BATT") (class "Default")
      (node (ref "BATT") (pin "1") (pinfunction "1_1") (pintype "passive"))
      (node (ref "C25") (pin "1") (pinfunction "1_1") (pintype "passive"))
      (node (ref "IC7") (pin "3") (pinfunction "IN_3") (pintype "input"))
      (node (ref "J2") (pin "1") (pinfunction "1_1") (pintype "passive"))
      (node (ref "OK1") (pin "1") (pinfunction "A_1") (pintype "passive"))
      (node (ref "R16") (pin "2") (pinfunction "2_2") (pintype "passive"))
      (node (ref "R17") (pin "1") (pinfunction "1_1") (pintype "passive"))
      (node (ref "R22") (pin "2") (pinfunction "2_2") (pintype "passive"))
      (node (ref "U$16") (pin "A0") (pinfunction "O_A0") (pintype "passive"))
      (node (ref "U1") (pin "5") (pinfunction "BAT_5") (pintype "bidirectional"))
    )
    (net (code "90") (name "unconnected-(J1-USBID-PadID1)") (class "Default")
      (node (ref "J1") (pin "ID1") (pinfunction "USBID_ID1") (pintype "bidirectional"))
    )
    (net (code "91") (name "unconnected-(LED1-BLUE-Pad4)") (class "Default")
      (node (ref "LED1") (pin "4") (pinfunction "BLUE_4") (pintype "bidirectional"))
    )
    (net (code "92") (name "unconnected-(SW1-S-PadP$3)") (class "Default")
      (node (ref "SW1") (pin "P$3") (pinfunction "S_P$3") (pintype "passive"))
    )
    (net (code "93") (name "unconnected-(SW1-S1-PadP$6)") (class "Default")
      (node (ref "SW1") (pin "P$6") (pinfunction "S1_P$6") (pintype "passive"))
    )
    (net (code "94") (name "unconnected-(U$1-PA15-Pad38)") (class "Default")
      (node (ref "U$1") (pin "38") (pinfunction "PA15_38") (pintype "bidirectional"))
    )
    (net (code "95") (name "unconnected-(U$1-PB4-Pad40)") (class "Default")
      (node (ref "U$1") (pin "40") (pinfunction "PB4_40") (pintype "bidirectional"))
    )
    (net (code "96") (name "unconnected-(U$1-PC13-Pad2)") (class "Default")
      (node (ref "U$1") (pin "2") (pinfunction "PC13_2") (pintype "bidirectional"))
    )
    (net (code "97") (name "unconnected-(U$16-S-PadB0)") (class "Default")
      (node (ref "U$16") (pin "B0") (pinfunction "S_B0") (pintype "passive"))
    )
    (net (code "98") (name "unconnected-(U$16-S1-PadB1)") (class "Default")
      (node (ref "U$16") (pin "B1") (pinfunction "S1_B1") (pintype "passive"))
    )
    (net (code "99") (name "unconnected-(U2-R232-Pad15)") (class "Default")
      (node (ref "U2") (pin "15") (pinfunction "R232_15") (pintype "bidirectional"))
    )
    (net (code "100") (name "unconnected-(U2-~{CTS}-Pad9)") (class "Default")
      (node (ref "U2") (pin "9") (pinfunction "~{CTS}_9") (pintype "bidirectional"))
    )
    (net (code "101") (name "unconnected-(U2-~{DCD}-Pad12)") (class "Default")
      (node (ref "U2") (pin "12") (pinfunction "~{DCD}_12") (pintype "bidirectional"))
    )
    (net (code "102") (name "unconnected-(U2-~{DSR}-Pad10)") (class "Default")
      (node (ref "U2") (pin "10") (pinfunction "~{DSR}_10") (pintype "bidirectional"))
    )
    (net (code "103") (name "unconnected-(U2-~{DTR}-Pad13)") (class "Default")
      (node (ref "U2") (pin "13") (pinfunction "~{DTR}_13") (pintype "bidirectional"))
    )
    (net (code "104") (name "unconnected-(U2-~{RI}-Pad11)") (class "Default")
      (node (ref "U2") (pin "11") (pinfunction "~{RI}_11") (pintype "bidirectional"))
    )
    (net (code "105") (name "unconnected-(U2-~{RTS}-Pad14)") (class "Default")
      (node (ref "U2") (pin "14") (pinfunction "~{RTS}_14") (pintype "bidirectional"))
    )
    (net (code "106") (name "unconnected-(U3-TD-Pad4)") (class "Default")
      (node (ref "U3") (pin "4") (pinfunction "TD_4") (pintype "output"))
    )
  )
)
